# RFTP1206.net
KiCad netlist of a schematic drawn in Altium Designer
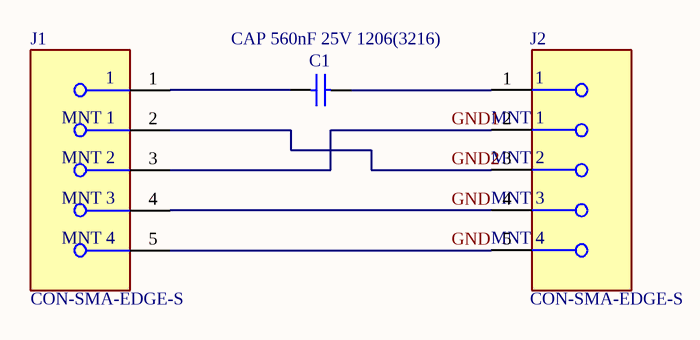
[diagram p0: RFTP1206.SchDoc]

(export (version "E")
  (design (tool "Eeschema 10.0.6"))
  (components
    (comp (ref "C1")
      (value "CAP 560nF 25V 1206(3216)")
      (footprint "CAPC1206(3216)170_M")
      (description "CAP 560nF 25V ±10% 1206 (3216 Metric) Thickness 1.7mm SMD")
      (fields (field (name "TOLERANCE") "Â±10%"))
      (libsource (lib "Altium Content Vault") (part "CAP"))
    )
    (comp (ref "J1")
      (value "CON-SMA-EDGE-S")
      (footprint "FP-CON-SMA-EDGE-S-MFG")
      (description "CONN SMA JACK STR EDGE MNT")
      (fields
        (field (name "OCTOPART") "https://octopart.com/con-sma-edge-s-rf+solutions-70967450")
        (field (name "MANUFACTURER") "RF Solutions Ltd.")
      )
      (libsource (lib "") (part "a163d97a771fcdd2fd1f1a9264c171f_1"))
    )
    (comp (ref "J2")
      (value "CON-SMA-EDGE-S")
      (footprint "FP-CON-SMA-EDGE-S-MFG")
      (description "CONN SMA JACK STR EDGE MNT")
      (fields
        (field (name "OCTOPART") "https://octopart.com/con-sma-edge-s-rf+solutions-70967450")
        (field (name "MANUFACTURER") "RF Solutions Ltd.")
      )
      (libsource (lib "Altium Content Vault") (part "a163d97a771fcdd2fd1f1a9264c171f"))
    )
  )
  (nets
    (net (code "1") (name "/GND") (class "Default")
      (node (ref "J1") (pin "4") (pinfunction "MNT_3_4") (pintype "passive"))
      (node (ref "J1") (pin "5") (pinfunction "MNT_4_5") (pintype "passive"))
      (node (ref "J2") (pin "4") (pinfunction "MNT_3_4") (pintype "passive"))
      (node (ref "J2") (pin "5") (pinfunction "MNT_4_5") (pintype "passive"))
    )
    (net (code "2") (name "/GND1") (class "Default")
      (node (ref "J1") (pin "3") (pinfunction "MNT_2_3") (pintype "passive"))
      (node (ref "J2") (pin "2") (pinfunction "MNT_1_2") (pintype "passive"))
    )
    (net (code "3") (name "/GND2") (class "Default")
      (node (ref "J1") (pin "2") (pinfunction "MNT_1_2") (pintype "passive"))
      (node (ref "J2") (pin "3") (pinfunction "MNT_2_3") (pintype "passive"))
    )
    (net (code "4") (name "Net-(C1-Pad1)") (class "Default")
      (node (ref "C1") (pin "1") (pinfunction "1_1") (pintype "passive"))
      (node (ref "J1") (pin "1") (pinfunction "1_1") (pintype "passive"))
    )
    (net (code "5") (name "Net-(C1-Pad2)") (class "Default")
      (node (ref "C1") (pin "2") (pinfunction "2_2") (pintype "passive"))
      (node (ref "J2") (pin "1") (pinfunction "1_1") (pintype "passive"))
    )
  )
)
